# hatino.net
KiCad netlist of a schematic drawn in EAGLE
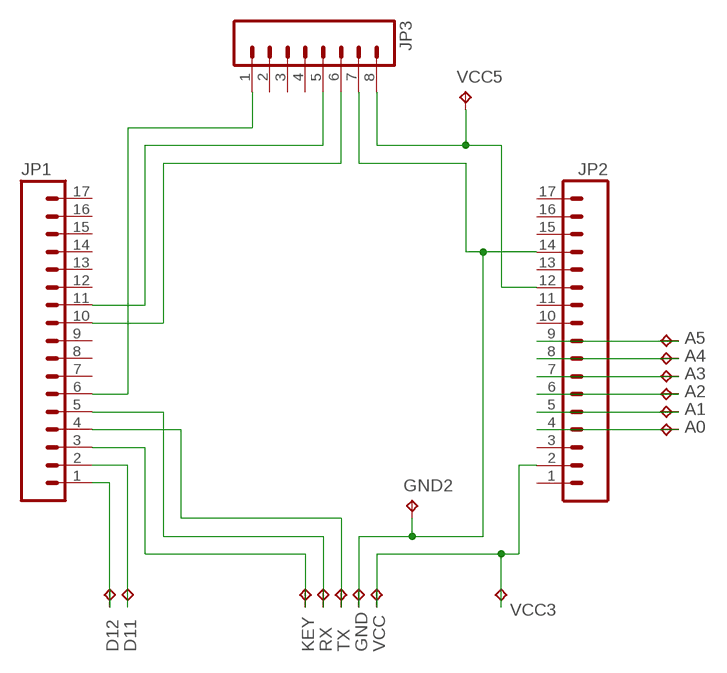
[diagram p0: schematic, sheet 1]

(export (version "E")
  (design (tool "Eeschema 10.0.6"))
  (components
    (comp (ref "A0")
      (value "TPPAD1-13Y")
      (footprint "eagle-import:P1-13Y")
      (libsource (lib "eagle-import") (part "TPPAD1-13Y"))
    )
    (comp (ref "A1")
      (value "TPPAD1-13Y")
      (footprint "eagle-import:P1-13Y")
      (libsource (lib "eagle-import") (part "TPPAD1-13Y"))
    )
    (comp (ref "A2")
      (value "TPPAD1-13Y")
      (footprint "eagle-import:P1-13Y")
      (libsource (lib "eagle-import") (part "TPPAD1-13Y"))
    )
    (comp (ref "A3")
      (value "TPPAD1-13Y")
      (footprint "eagle-import:P1-13Y")
      (libsource (lib "eagle-import") (part "TPPAD1-13Y"))
    )
    (comp (ref "A4")
      (value "TPPAD1-13Y")
      (footprint "eagle-import:P1-13Y")
      (libsource (lib "eagle-import") (part "TPPAD1-13Y"))
    )
    (comp (ref "A5")
      (value "TPPAD1-13Y")
      (footprint "eagle-import:P1-13Y")
      (libsource (lib "eagle-import") (part "TPPAD1-13Y"))
    )
    (comp (ref "D11")
      (value "TPPAD1-13Y")
      (footprint "eagle-import:P1-13Y")
      (libsource (lib "eagle-import") (part "TPPAD1-13Y"))
    )
    (comp (ref "D12")
      (value "TPPAD1-13Y")
      (footprint "eagle-import:P1-13Y")
      (libsource (lib "eagle-import") (part "TPPAD1-13Y"))
    )
    (comp (ref "GND")
      (value "TPPAD1-13Y")
      (footprint "eagle-import:P1-13Y")
      (libsource (lib "eagle-import") (part "TPPAD1-13Y"))
    )
    (comp (ref "GND2")
      (value "TPPAD1-13Y")
      (footprint "eagle-import:P1-13Y")
      (libsource (lib "eagle-import") (part "TPPAD1-13Y"))
    )
    (comp (ref "JP1")
      (value "M17")
      (footprint "eagle-import:1X17")
      (libsource (lib "eagle-import") (part "M17"))
    )
    (comp (ref "JP2")
      (value "M17")
      (footprint "eagle-import:1X17")
      (libsource (lib "eagle-import") (part "M17"))
    )
    (comp (ref "JP3")
      (value "M08")
      (footprint "eagle-import:1X08_ROUND")
      (libsource (lib "eagle-import") (part "M08"))
    )
    (comp (ref "KEY")
      (value "TPPAD1-13Y")
      (footprint "eagle-import:P1-13Y")
      (libsource (lib "eagle-import") (part "TPPAD1-13Y"))
    )
    (comp (ref "RX")
      (value "TPPAD1-13Y")
      (footprint "eagle-import:P1-13Y")
      (libsource (lib "eagle-import") (part "TPPAD1-13Y"))
    )
    (comp (ref "TX")
      (value "TPPAD1-13Y")
      (footprint "eagle-import:P1-13Y")
      (libsource (lib "eagle-import") (part "TPPAD1-13Y"))
    )
    (comp (ref "VCC")
      (value "TPPAD1-13Y")
      (footprint "eagle-import:P1-13Y")
      (libsource (lib "eagle-import") (part "TPPAD1-13Y"))
    )
    (comp (ref "VCC3")
      (value "TPPAD1-13Y")
      (footprint "eagle-import:P1-13Y")
      (libsource (lib "eagle-import") (part "TPPAD1-13Y"))
    )
    (comp (ref "VCC5")
      (value "TPPAD1-13Y")
      (footprint "eagle-import:P1-13Y")
      (libsource (lib "eagle-import") (part "TPPAD1-13Y"))
    )
  )
  (nets
    (net (code "1") (name "Net-(A0-PadTP)") (class "Default")
      (node (ref "A0") (pin "TP") (pinfunction "TP_TP") (pintype "input"))
      (node (ref "JP2") (pin "4") (pinfunction "4_4") (pintype "passive"))
    )
    (net (code "2") (name "Net-(A1-PadTP)") (class "Default")
      (node (ref "A1") (pin "TP") (pinfunction "TP_TP") (pintype "input"))
      (node (ref "JP2") (pin "5") (pinfunction "5_5") (pintype "passive"))
    )
    (net (code "3") (name "Net-(A2-PadTP)") (class "Default")
      (node (ref "A2") (pin "TP") (pinfunction "TP_TP") (pintype "input"))
      (node (ref "JP2") (pin "6") (pinfunction "6_6") (pintype "passive"))
    )
    (net (code "4") (name "Net-(A3-PadTP)") (class "Default")
      (node (ref "A3") (pin "TP") (pinfunction "TP_TP") (pintype "input"))
      (node (ref "JP2") (pin "7") (pinfunction "7_7") (pintype "passive"))
    )
    (net (code "5") (name "Net-(A4-PadTP)") (class "Default")
      (node (ref "A4") (pin "TP") (pinfunction "TP_TP") (pintype "input"))
      (node (ref "JP2") (pin "8") (pinfunction "8_8") (pintype "passive"))
    )
    (net (code "6") (name "Net-(A5-PadTP)") (class "Default")
      (node (ref "A5") (pin "TP") (pinfunction "TP_TP") (pintype "input"))
      (node (ref "JP2") (pin "9") (pinfunction "9_9") (pintype "passive"))
    )
    (net (code "7") (name "Net-(D11-PadTP)") (class "Default")
      (node (ref "D11") (pin "TP") (pinfunction "TP_TP") (pintype "input"))
      (node (ref "JP1") (pin "2") (pinfunction "2_2") (pintype "passive"))
    )
    (net (code "8") (name "Net-(D12-PadTP)") (class "Default")
      (node (ref "D12") (pin "TP") (pinfunction "TP_TP") (pintype "input"))
      (node (ref "JP1") (pin "1") (pinfunction "1_1") (pintype "passive"))
    )
    (net (code "9") (name "Net-(GND-PadTP)") (class "Default")
      (node (ref "GND") (pin "TP") (pinfunction "TP_TP") (pintype "input"))
      (node (ref "GND2") (pin "TP") (pinfunction "TP_TP") (pintype "input"))
      (node (ref "JP2") (pin "14") (pinfunction "14_14") (pintype "passive"))
      (node (ref "JP3") (pin "7") (pinfunction "7_7") (pintype "passive"))
    )
    (net (code "10") (name "Net-(JP1-Pad3)") (class "Default")
      (node (ref "JP1") (pin "3") (pinfunction "3_3") (pintype "passive"))
      (node (ref "KEY") (pin "TP") (pinfunction "TP_TP") (pintype "input"))
    )
    (net (code "11") (name "Net-(JP1-Pad4)") (class "Default")
      (node (ref "JP1") (pin "4") (pinfunction "4_4") (pintype "passive"))
      (node (ref "TX") (pin "TP") (pinfunction "TP_TP") (pintype "input"))
    )
    (net (code "12") (name "Net-(JP1-Pad5)") (class "Default")
      (node (ref "JP1") (pin "5") (pinfunction "5_5") (pintype "passive"))
      (node (ref "RX") (pin "TP") (pinfunction "TP_TP") (pintype "input"))
    )
    (net (code "13") (name "Net-(JP1-Pad6)") (class "Default")
      (node (ref "JP1") (pin "6") (pinfunction "6_6") (pintype "passive"))
      (node (ref "JP3") (pin "1") (pinfunction "1_1") (pintype "passive"))
    )
    (net (code "14") (name "Net-(JP1-Pad10)") (class "Default")
      (node (ref "JP1") (pin "10") (pinfunction "10_10") (pintype "passive"))
      (node (ref "JP3") (pin "6") (pinfunction "6_6") (pintype "passive"))
    )
    (net (code "15") (name "Net-(JP1-Pad11)") (class "Default")
      (node (ref "JP1") (pin "11") (pinfunction "11_11") (pintype "passive"))
      (node (ref "JP3") (pin "5") (pinfunction "5_5") (pintype "passive"))
    )
    (net (code "16") (name "Net-(JP2-Pad2)") (class "Default")
      (node (ref "JP2") (pin "2") (pinfunction "2_2") (pintype "passive"))
      (node (ref "VCC") (pin "TP") (pinfunction "TP_TP") (pintype "input"))
      (node (ref "VCC3") (pin "TP") (pinfunction "TP_TP") (pintype "input"))
    )
    (net (code "17") (name "Net-(JP2-Pad12)") (class "Default")
      (node (ref "JP2") (pin "12") (pinfunction "12_12") (pintype "passive"))
      (node (ref "JP3") (pin "8") (pinfunction "8_8") (pintype "passive"))
      (node (ref "VCC5") (pin "TP") (pinfunction "TP_TP") (pintype "input"))
    )
    (net (code "18") (name "unconnected-(JP1-Pad7)") (class "Default")
      (node (ref "JP1") (pin "7") (pinfunction "7_7") (pintype "passive"))
    )
    (net (code "19") (name "unconnected-(JP1-Pad8)") (class "Default")
      (node (ref "JP1") (pin "8") (pinfunction "8_8") (pintype "passive"))
    )
    (net (code "20") (name "unconnected-(JP1-Pad9)") (class "Default")
      (node (ref "JP1") (pin "9") (pinfunction "9_9") (pintype "passive"))
    )
    (net (code "21") (name "unconnected-(JP1-Pad12)") (class "Default")
      (node (ref "JP1") (pin "12") (pinfunction "12_12") (pintype "passive"))
    )
    (net (code "22") (name "unconnected-(JP1-Pad13)") (class "Default")
      (node (ref "JP1") (pin "13") (pinfunction "13_13") (pintype "passive"))
    )
    (net (code "23") (name "unconnected-(JP1-Pad14)") (class "Default")
      (node (ref "JP1") (pin "14") (pinfunction "14_14") (pintype "passive"))
    )
    (net (code "24") (name "unconnected-(JP1-Pad15)") (class "Default")
      (node (ref "JP1") (pin "15") (pinfunction "15_15") (pintype "passive"))
    )
    (net (code "25") (name "unconnected-(JP1-Pad16)") (class "Default")
      (node (ref "JP1") (pin "16") (pinfunction "16_16") (pintype "passive"))
    )
    (net (code "26") (name "unconnected-(JP1-Pad17)") (class "Default")
      (node (ref "JP1") (pin "17") (pinfunction "17_17") (pintype "passive"))
    )
    (net (code "27") (name "unconnected-(JP2-Pad1)") (class "Default")
      (node (ref "JP2") (pin "1") (pinfunction "1_1") (pintype "passive"))
    )
    (net (code "28") (name "unconnected-(JP2-Pad3)") (class "Default")
      (node (ref "JP2") (pin "3") (pinfunction "3_3") (pintype "passive"))
    )
    (net (code "29") (name "unconnected-(JP2-Pad10)") (class "Default")
      (node (ref "JP2") (pin "10") (pinfunction "10_10") (pintype "passive"))
    )
    (net (code "30") (name "unconnected-(JP2-Pad11)") (class "Default")
      (node (ref "JP2") (pin "11") (pinfunction "11_11") (pintype "passive"))
    )
    (net (code "31") (name "unconnected-(JP2-Pad13)") (class "Default")
      (node (ref "JP2") (pin "13") (pinfunction "13_13") (pintype "passive"))
    )
    (net (code "32") (name "unconnected-(JP2-Pad15)") (class "Default")
      (node (ref "JP2") (pin "15") (pinfunction "15_15") (pintype "passive"))
    )
    (net (code "33") (name "unconnected-(JP2-Pad16)") (class "Default")
      (node (ref "JP2") (pin "16") (pinfunction "16_16") (pintype "passive"))
    )
    (net (code "34") (name "unconnected-(JP2-Pad17)") (class "Default")
      (node (ref "JP2") (pin "17") (pinfunction "17_17") (pintype "passive"))
    )
    (net (code "35") (name "unconnected-(JP3-Pad2)") (class "Default")
      (node (ref "JP3") (pin "2") (pinfunction "2_2") (pintype "passive"))
    )
    (net (code "36") (name "unconnected-(JP3-Pad3)") (class "Default")
      (node (ref "JP3") (pin "3") (pinfunction "3_3") (pintype "passive"))
    )
    (net (code "37") (name "unconnected-(JP3-Pad4)") (class "Default")
      (node (ref "JP3") (pin "4") (pinfunction "4_4") (pintype "passive"))
    )
  )
)
